# SCH_New_Project4_2022-07-20.net
KiCad netlist of a schematic drawn in EasyEDA
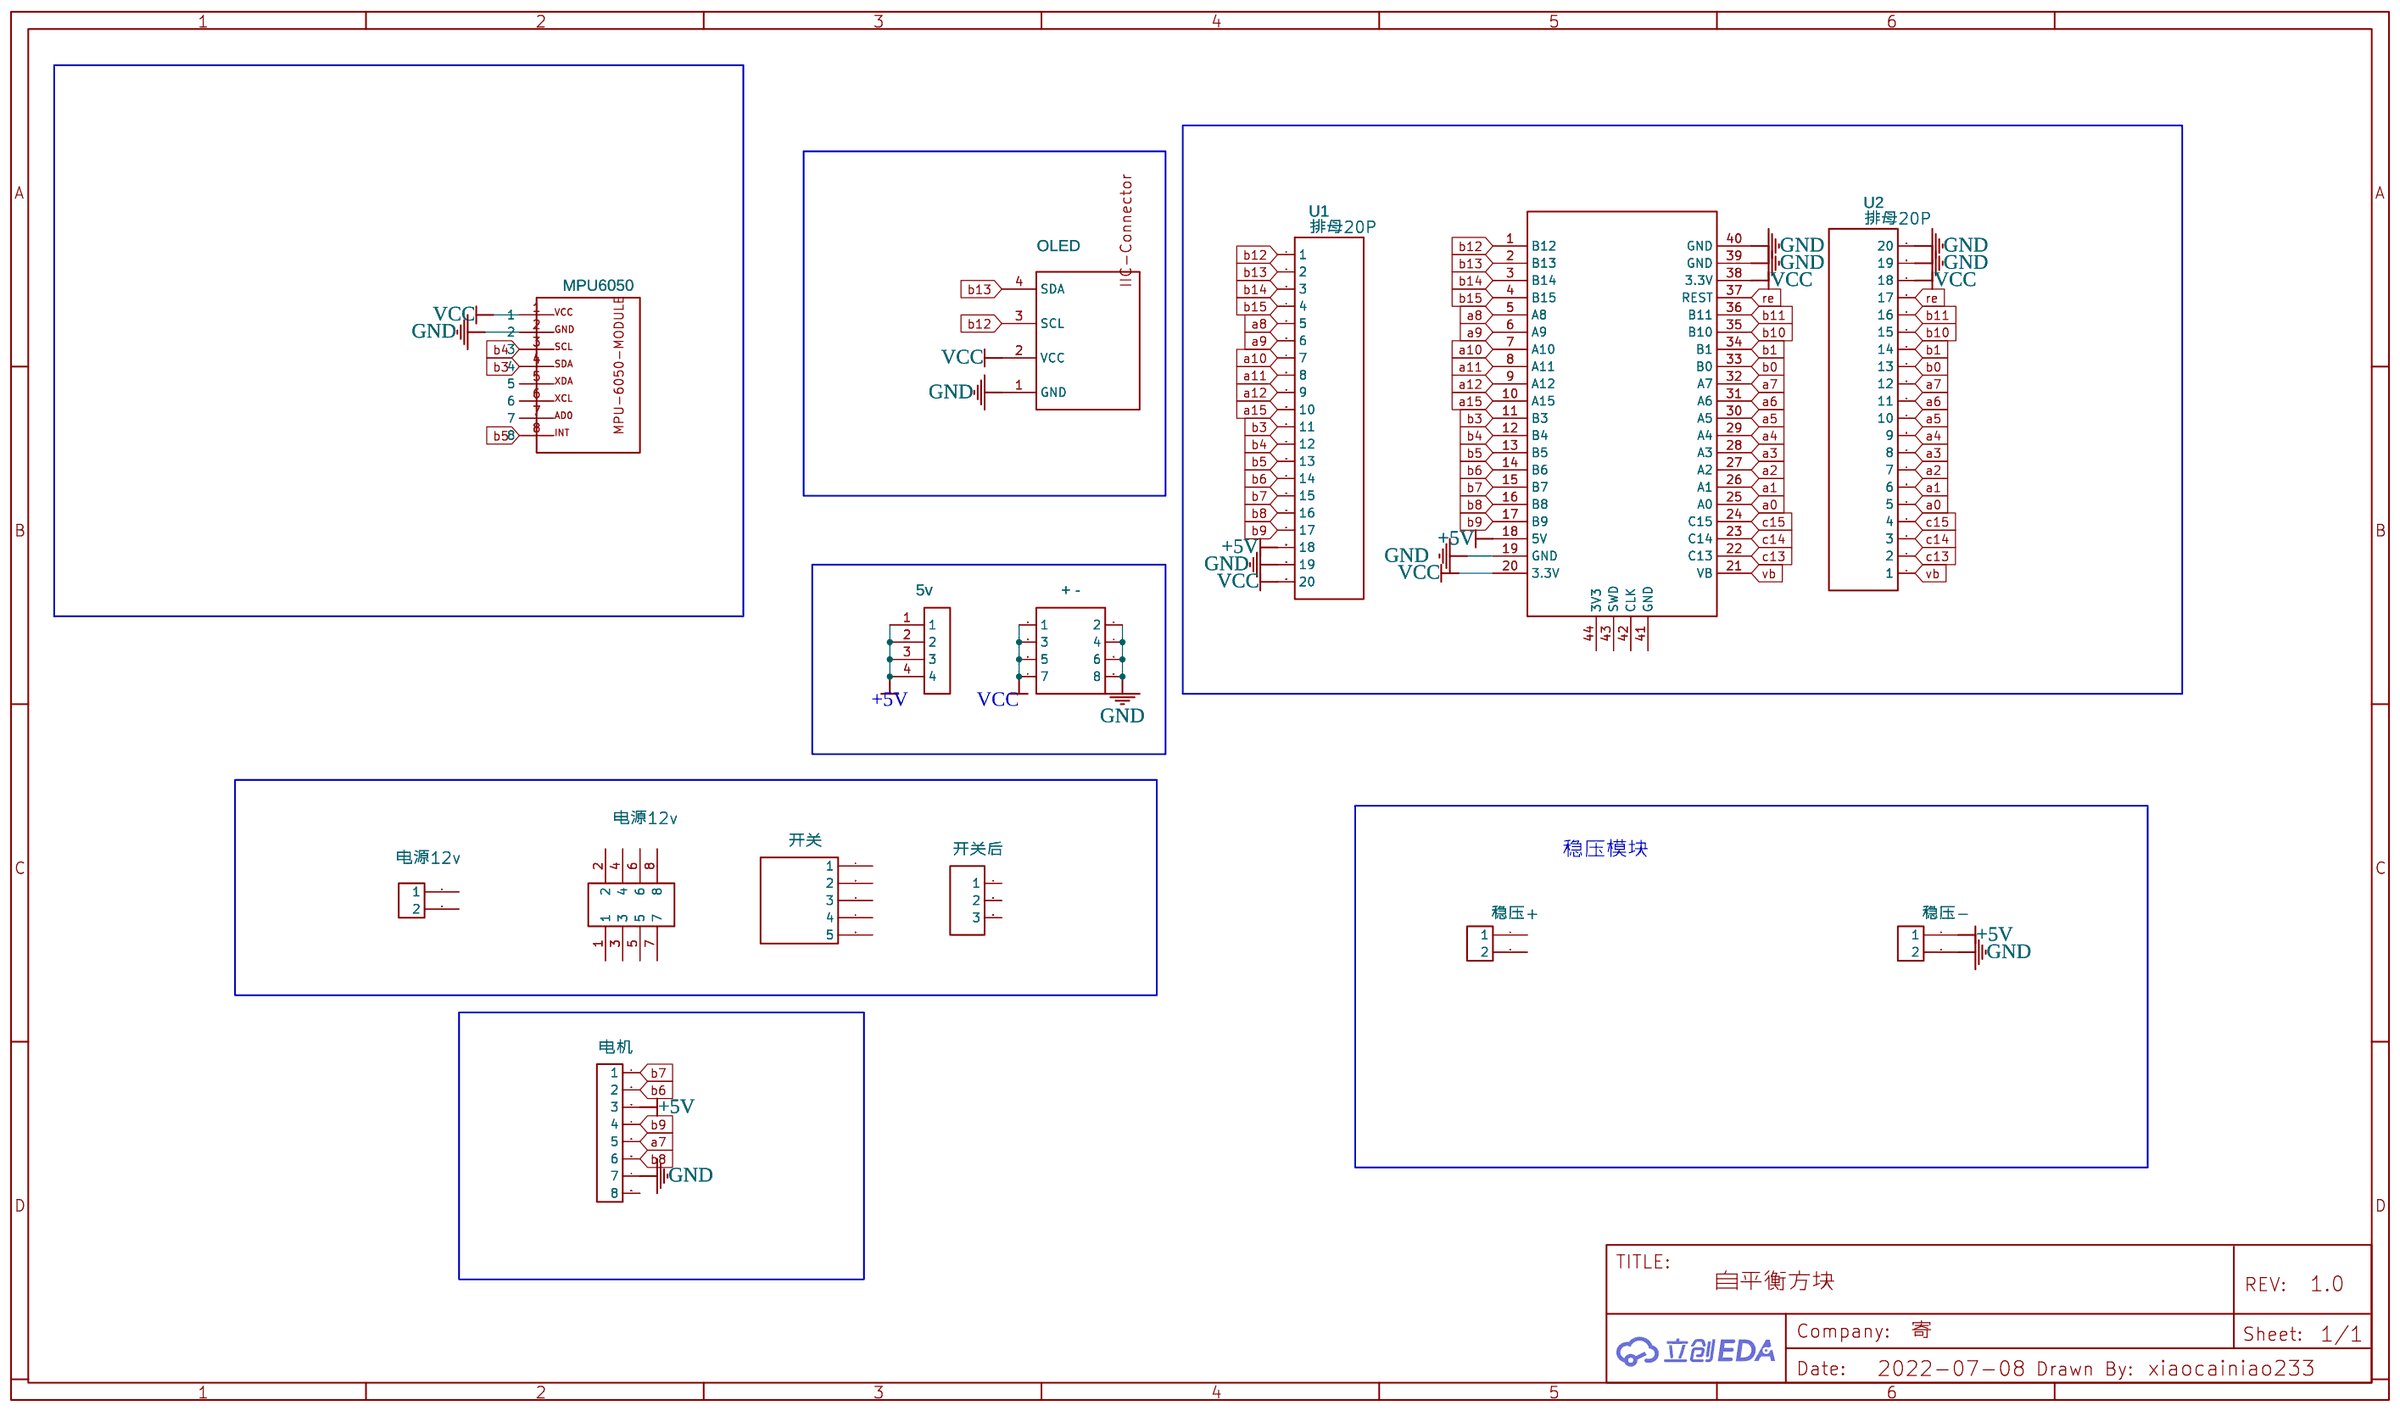
[diagram p0: schematic sheet]

(export (version "E")
  (design (tool "Eeschema 10.0.6"))
  (components
    (comp (ref "AAAAU1") (value "MPU6050") (libsource (lib "") (part "MPU6050")))
    (comp (ref "ASDFGUUU1") (value "STM32F103C8T6最小系统板") (libsource (lib "") (part "Unknown_930_-560")))
    (comp (ref "H1")
      (value "+ -")
      (fields
        (field (name "BOM_Manufacturer Part") "220S-2*4P H=8.5MM Ytype Gold-plated")
        (field (name "BOM_Supplier Part") "C124422")
      )
      (libsource (lib "") (part "2.54排母_2X4"))
    )
    (comp (ref "H2")
      (value "5v")
      (fields (field (name "BOM_Supplier Part") "C169817"))
      (libsource (lib "") (part "排针排母4P"))
    )
    (comp (ref "H3")
      (value "电源12v")
      (fields (field (name "BOM_Supplier Part") "C169817"))
      (libsource (lib "") (part "排针排母2*4P"))
    )
    (comp (ref "J1")
      (value "电源12v")
      (fields (field (name "BOM_Supplier Part") "C115245"))
      (libsource (lib "") (part "排针排母1*2P"))
    )
    (comp (ref "J2")
      (value "开关")
      (fields (field (name "BOM_Supplier Part") "C115245"))
      (libsource (lib "") (part "排针排母1*5P"))
    )
    (comp (ref "J3")
      (value "电机")
      (fields (field (name "BOM_Supplier Part") "C115245"))
      (libsource (lib "") (part "排针排母1*8P"))
    )
    (comp (ref "J4")
      (value "稳压+")
      (fields (field (name "BOM_Supplier Part") "C115245"))
      (libsource (lib "") (part "排针排母1*2P"))
    )
    (comp (ref "J5")
      (value "稳压-")
      (fields (field (name "BOM_Supplier Part") "C115245"))
      (libsource (lib "") (part "排针排母1*2P"))
    )
    (comp (ref "J6")
      (value "开关后")
      (fields (field (name "BOM_Manufacturer Part") "Headers") (field (name "BOM_Supplier Part") "C57369"))
      (libsource (lib "") (part "排针排母1*3P"))
    )
    (comp (ref "OLED")
      (value "0.96OLED")
      (fields
        (field (name "BOM_Manufacturer Part") "0.96OLED_4P_MODULE_JX")
        (field (name "BOM_Supplier Part") "C9900004566")
      )
      (libsource (lib "") (part "0.96OLED_4P_MODULE_JX"))
    )
    (comp (ref "U1") (value "排母20P") (libsource (lib "") (part "排母20P")))
    (comp (ref "U2") (value "排母20P") (libsource (lib "") (part "排母20P_1")))
  )
  (nets
    (net (code "1") (name "+5V") (class "Default")
      (node (ref "ASDFGUUU1") (pin "18") (pinfunction "5V_18") (pintype "unspecified"))
      (node (ref "H2") (pin "1") (pinfunction "1_1") (pintype "unspecified"))
      (node (ref "H2") (pin "2") (pinfunction "2_2") (pintype "unspecified"))
      (node (ref "H2") (pin "3") (pinfunction "3_3") (pintype "unspecified"))
      (node (ref "H2") (pin "4") (pinfunction "4_4") (pintype "unspecified"))
      (node (ref "J3") (pin "3") (pinfunction "3_3") (pintype "unspecified"))
      (node (ref "J5") (pin "1") (pinfunction "1_1") (pintype "unspecified"))
      (node (ref "U1") (pin "18") (pinfunction "18_18") (pintype "input"))
    )
    (net (code "2") (name "GND") (class "Default")
      (node (ref "AAAAU1") (pin "2") (pinfunction "2_2") (pintype "unspecified"))
      (node (ref "ASDFGUUU1") (pin "19") (pinfunction "GND_19") (pintype "unspecified"))
      (node (ref "ASDFGUUU1") (pin "39") (pinfunction "GND_39") (pintype "unspecified"))
      (node (ref "ASDFGUUU1") (pin "40") (pinfunction "GND_40") (pintype "unspecified"))
      (node (ref "H1") (pin "2") (pinfunction "2_2") (pintype "unspecified"))
      (node (ref "H1") (pin "4") (pinfunction "4_4") (pintype "unspecified"))
      (node (ref "H1") (pin "6") (pinfunction "6_6") (pintype "unspecified"))
      (node (ref "H1") (pin "8") (pinfunction "8_8") (pintype "unspecified"))
      (node (ref "J3") (pin "7") (pinfunction "7_7") (pintype "unspecified"))
      (node (ref "J5") (pin "2") (pinfunction "2_2") (pintype "unspecified"))
      (node (ref "OLED") (pin "1") (pinfunction "GND_1") (pintype "unspecified"))
      (node (ref "U1") (pin "19") (pinfunction "19_19") (pintype "input"))
      (node (ref "U2") (pin "19") (pinfunction "19_19") (pintype "input"))
      (node (ref "U2") (pin "20") (pinfunction "20_20") (pintype "input"))
    )
    (net (code "3") (name "VCC") (class "Default")
      (node (ref "AAAAU1") (pin "1") (pinfunction "1_1") (pintype "unspecified"))
      (node (ref "ASDFGUUU1") (pin "20") (pinfunction "3.3V_20") (pintype "unspecified"))
      (node (ref "ASDFGUUU1") (pin "38") (pinfunction "3.3V_38") (pintype "unspecified"))
      (node (ref "H1") (pin "1") (pinfunction "1_1") (pintype "unspecified"))
      (node (ref "H1") (pin "3") (pinfunction "3_3") (pintype "unspecified"))
      (node (ref "H1") (pin "5") (pinfunction "5_5") (pintype "unspecified"))
      (node (ref "H1") (pin "7") (pinfunction "7_7") (pintype "unspecified"))
      (node (ref "OLED") (pin "2") (pinfunction "VCC_2") (pintype "unspecified"))
      (node (ref "U1") (pin "20") (pinfunction "20_20") (pintype "input"))
      (node (ref "U2") (pin "18") (pinfunction "18_18") (pintype "input"))
    )
    (net (code "4") (name "a0") (class "Default")
      (node (ref "ASDFGUUU1") (pin "25") (pinfunction "A0_25") (pintype "unspecified"))
      (node (ref "U2") (pin "5") (pinfunction "5_5") (pintype "input"))
    )
    (net (code "5") (name "a1") (class "Default")
      (node (ref "ASDFGUUU1") (pin "26") (pinfunction "A1_26") (pintype "unspecified"))
      (node (ref "U2") (pin "6") (pinfunction "6_6") (pintype "input"))
    )
    (net (code "6") (name "a2") (class "Default")
      (node (ref "ASDFGUUU1") (pin "27") (pinfunction "A2_27") (pintype "unspecified"))
      (node (ref "U2") (pin "7") (pinfunction "7_7") (pintype "input"))
    )
    (net (code "7") (name "a3") (class "Default")
      (node (ref "ASDFGUUU1") (pin "28") (pinfunction "A3_28") (pintype "unspecified"))
      (node (ref "U2") (pin "8") (pinfunction "8_8") (pintype "input"))
    )
    (net (code "8") (name "a4") (class "Default")
      (node (ref "ASDFGUUU1") (pin "29") (pinfunction "A4_29") (pintype "unspecified"))
      (node (ref "U2") (pin "9") (pinfunction "9_9") (pintype "input"))
    )
    (net (code "9") (name "a5") (class "Default")
      (node (ref "ASDFGUUU1") (pin "30") (pinfunction "A5_30") (pintype "unspecified"))
      (node (ref "U2") (pin "10") (pinfunction "10_10") (pintype "input"))
    )
    (net (code "10") (name "a6") (class "Default")
      (node (ref "ASDFGUUU1") (pin "31") (pinfunction "A6_31") (pintype "unspecified"))
      (node (ref "U2") (pin "11") (pinfunction "11_11") (pintype "input"))
    )
    (net (code "11") (name "a7") (class "Default")
      (node (ref "ASDFGUUU1") (pin "32") (pinfunction "A7_32") (pintype "unspecified"))
      (node (ref "J3") (pin "5") (pinfunction "5_5") (pintype "unspecified"))
      (node (ref "U2") (pin "12") (pinfunction "12_12") (pintype "input"))
    )
    (net (code "12") (name "a8") (class "Default")
      (node (ref "ASDFGUUU1") (pin "5") (pinfunction "A8_5") (pintype "unspecified"))
      (node (ref "U1") (pin "5") (pinfunction "5_5") (pintype "input"))
    )
    (net (code "13") (name "a9") (class "Default")
      (node (ref "ASDFGUUU1") (pin "6") (pinfunction "A9_6") (pintype "unspecified"))
      (node (ref "U1") (pin "6") (pinfunction "6_6") (pintype "input"))
    )
    (net (code "14") (name "a10") (class "Default")
      (node (ref "ASDFGUUU1") (pin "7") (pinfunction "A10_7") (pintype "unspecified"))
      (node (ref "U1") (pin "7") (pinfunction "7_7") (pintype "input"))
    )
    (net (code "15") (name "a11") (class "Default")
      (node (ref "ASDFGUUU1") (pin "8") (pinfunction "A11_8") (pintype "unspecified"))
      (node (ref "U1") (pin "8") (pinfunction "8_8") (pintype "input"))
    )
    (net (code "16") (name "a12") (class "Default")
      (node (ref "ASDFGUUU1") (pin "9") (pinfunction "A12_9") (pintype "unspecified"))
      (node (ref "U1") (pin "9") (pinfunction "9_9") (pintype "input"))
    )
    (net (code "17") (name "a15") (class "Default")
      (node (ref "ASDFGUUU1") (pin "10") (pinfunction "A15_10") (pintype "unspecified"))
      (node (ref "U1") (pin "10") (pinfunction "10_10") (pintype "input"))
    )
    (net (code "18") (name "b0") (class "Default")
      (node (ref "ASDFGUUU1") (pin "33") (pinfunction "B0_33") (pintype "unspecified"))
      (node (ref "U2") (pin "13") (pinfunction "13_13") (pintype "input"))
    )
    (net (code "19") (name "b1") (class "Default")
      (node (ref "ASDFGUUU1") (pin "34") (pinfunction "B1_34") (pintype "unspecified"))
      (node (ref "U2") (pin "14") (pinfunction "14_14") (pintype "input"))
    )
    (net (code "20") (name "b3") (class "Default")
      (node (ref "AAAAU1") (pin "4") (pinfunction "4_4") (pintype "unspecified"))
      (node (ref "ASDFGUUU1") (pin "11") (pinfunction "B3_11") (pintype "unspecified"))
      (node (ref "U1") (pin "11") (pinfunction "11_11") (pintype "input"))
    )
    (net (code "21") (name "b4") (class "Default")
      (node (ref "AAAAU1") (pin "3") (pinfunction "3_3") (pintype "unspecified"))
      (node (ref "ASDFGUUU1") (pin "12") (pinfunction "B4_12") (pintype "unspecified"))
      (node (ref "U1") (pin "12") (pinfunction "12_12") (pintype "input"))
    )
    (net (code "22") (name "b5") (class "Default")
      (node (ref "AAAAU1") (pin "8") (pinfunction "8_8") (pintype "unspecified"))
      (node (ref "ASDFGUUU1") (pin "13") (pinfunction "B5_13") (pintype "unspecified"))
      (node (ref "U1") (pin "13") (pinfunction "13_13") (pintype "input"))
    )
    (net (code "23") (name "b6") (class "Default")
      (node (ref "ASDFGUUU1") (pin "14") (pinfunction "B6_14") (pintype "unspecified"))
      (node (ref "J3") (pin "2") (pinfunction "2_2") (pintype "unspecified"))
      (node (ref "U1") (pin "14") (pinfunction "14_14") (pintype "input"))
    )
    (net (code "24") (name "b7") (class "Default")
      (node (ref "ASDFGUUU1") (pin "15") (pinfunction "B7_15") (pintype "unspecified"))
      (node (ref "J3") (pin "1") (pinfunction "1_1") (pintype "unspecified"))
      (node (ref "U1") (pin "15") (pinfunction "15_15") (pintype "input"))
    )
    (net (code "25") (name "b8") (class "Default")
      (node (ref "ASDFGUUU1") (pin "16") (pinfunction "B8_16") (pintype "unspecified"))
      (node (ref "J3") (pin "6") (pinfunction "6_6") (pintype "unspecified"))
      (node (ref "U1") (pin "16") (pinfunction "16_16") (pintype "input"))
    )
    (net (code "26") (name "b9") (class "Default")
      (node (ref "ASDFGUUU1") (pin "17") (pinfunction "B9_17") (pintype "unspecified"))
      (node (ref "J3") (pin "4") (pinfunction "4_4") (pintype "unspecified"))
      (node (ref "U1") (pin "17") (pinfunction "17_17") (pintype "input"))
    )
    (net (code "27") (name "b10") (class "Default")
      (node (ref "ASDFGUUU1") (pin "35") (pinfunction "B10_35") (pintype "unspecified"))
      (node (ref "U2") (pin "15") (pinfunction "15_15") (pintype "input"))
    )
    (net (code "28") (name "b11") (class "Default")
      (node (ref "ASDFGUUU1") (pin "36") (pinfunction "B11_36") (pintype "unspecified"))
      (node (ref "U2") (pin "16") (pinfunction "16_16") (pintype "input"))
    )
    (net (code "29") (name "b12") (class "Default")
      (node (ref "ASDFGUUU1") (pin "1") (pinfunction "B12_1") (pintype "unspecified"))
      (node (ref "OLED") (pin "3") (pinfunction "SCL_3") (pintype "unspecified"))
      (node (ref "U1") (pin "1") (pinfunction "1_1") (pintype "input"))
    )
    (net (code "30") (name "b13") (class "Default")
      (node (ref "ASDFGUUU1") (pin "2") (pinfunction "B13_2") (pintype "unspecified"))
      (node (ref "OLED") (pin "4") (pinfunction "SDA_4") (pintype "unspecified"))
      (node (ref "U1") (pin "2") (pinfunction "2_2") (pintype "input"))
    )
    (net (code "31") (name "b14") (class "Default")
      (node (ref "ASDFGUUU1") (pin "3") (pinfunction "B14_3") (pintype "unspecified"))
      (node (ref "U1") (pin "3") (pinfunction "3_3") (pintype "input"))
    )
    (net (code "32") (name "b15") (class "Default")
      (node (ref "ASDFGUUU1") (pin "4") (pinfunction "B15_4") (pintype "unspecified"))
      (node (ref "U1") (pin "4") (pinfunction "4_4") (pintype "input"))
    )
    (net (code "33") (name "c13") (class "Default")
      (node (ref "ASDFGUUU1") (pin "22") (pinfunction "C13_22") (pintype "unspecified"))
      (node (ref "U2") (pin "2") (pinfunction "2_2") (pintype "input"))
    )
    (net (code "34") (name "c14") (class "Default")
      (node (ref "ASDFGUUU1") (pin "23") (pinfunction "C14_23") (pintype "unspecified"))
      (node (ref "U2") (pin "3") (pinfunction "3_3") (pintype "input"))
    )
    (net (code "35") (name "c15") (class "Default")
      (node (ref "ASDFGUUU1") (pin "24") (pinfunction "C15_24") (pintype "unspecified"))
      (node (ref "U2") (pin "4") (pinfunction "4_4") (pintype "input"))
    )
    (net (code "36") (name "re") (class "Default")
      (node (ref "ASDFGUUU1") (pin "37") (pinfunction "REST_37") (pintype "unspecified"))
      (node (ref "U2") (pin "17") (pinfunction "17_17") (pintype "input"))
    )
    (net (code "37") (name "unconnected-(AAAAU1-Pad5)") (class "Default")
      (node (ref "AAAAU1") (pin "5") (pinfunction "5_5") (pintype "unspecified"))
    )
    (net (code "38") (name "unconnected-(AAAAU1-Pad6)") (class "Default")
      (node (ref "AAAAU1") (pin "6") (pinfunction "6_6") (pintype "unspecified"))
    )
    (net (code "39") (name "unconnected-(AAAAU1-Pad7)") (class "Default")
      (node (ref "AAAAU1") (pin "7") (pinfunction "7_7") (pintype "unspecified"))
    )
    (net (code "40") (name "unconnected-(ASDFGUUU1-3V3-Pad44)") (class "Default")
      (node (ref "ASDFGUUU1") (pin "44") (pinfunction "3V3_44") (pintype "unspecified"))
    )
    (net (code "41") (name "unconnected-(ASDFGUUU1-CLK-Pad42)") (class "Default")
      (node (ref "ASDFGUUU1") (pin "42") (pinfunction "CLK_42") (pintype "unspecified"))
    )
    (net (code "42") (name "unconnected-(ASDFGUUU1-GND-Pad41)") (class "Default")
      (node (ref "ASDFGUUU1") (pin "41") (pinfunction "GND_41") (pintype "unspecified"))
    )
    (net (code "43") (name "unconnected-(ASDFGUUU1-SWD-Pad43)") (class "Default")
      (node (ref "ASDFGUUU1") (pin "43") (pinfunction "SWD_43") (pintype "unspecified"))
    )
    (net (code "44") (name "unconnected-(H3-Pad1)") (class "Default")
      (node (ref "H3") (pin "1") (pinfunction "1_1") (pintype "unspecified"))
    )
    (net (code "45") (name "unconnected-(H3-Pad2)") (class "Default")
      (node (ref "H3") (pin "2") (pinfunction "2_2") (pintype "unspecified"))
    )
    (net (code "46") (name "unconnected-(H3-Pad3)") (class "Default")
      (node (ref "H3") (pin "3") (pinfunction "3_3") (pintype "unspecified"))
    )
    (net (code "47") (name "unconnected-(H3-Pad4)") (class "Default")
      (node (ref "H3") (pin "4") (pinfunction "4_4") (pintype "unspecified"))
    )
    (net (code "48") (name "unconnected-(H3-Pad5)") (class "Default")
      (node (ref "H3") (pin "5") (pinfunction "5_5") (pintype "unspecified"))
    )
    (net (code "49") (name "unconnected-(H3-Pad6)") (class "Default")
      (node (ref "H3") (pin "6") (pinfunction "6_6") (pintype "unspecified"))
    )
    (net (code "50") (name "unconnected-(H3-Pad7)") (class "Default")
      (node (ref "H3") (pin "7") (pinfunction "7_7") (pintype "unspecified"))
    )
    (net (code "51") (name "unconnected-(H3-Pad8)") (class "Default")
      (node (ref "H3") (pin "8") (pinfunction "8_8") (pintype "unspecified"))
    )
    (net (code "52") (name "unconnected-(J1-Pad1)") (class "Default")
      (node (ref "J1") (pin "1") (pinfunction "1_1") (pintype "unspecified"))
    )
    (net (code "53") (name "unconnected-(J1-Pad2)") (class "Default")
      (node (ref "J1") (pin "2") (pinfunction "2_2") (pintype "unspecified"))
    )
    (net (code "54") (name "unconnected-(J2-Pad1)") (class "Default")
      (node (ref "J2") (pin "1") (pinfunction "1_1") (pintype "unspecified"))
    )
    (net (code "55") (name "unconnected-(J2-Pad2)") (class "Default")
      (node (ref "J2") (pin "2") (pinfunction "2_2") (pintype "unspecified"))
    )
    (net (code "56") (name "unconnected-(J2-Pad3)") (class "Default")
      (node (ref "J2") (pin "3") (pinfunction "3_3") (pintype "unspecified"))
    )
    (net (code "57") (name "unconnected-(J2-Pad4)") (class "Default")
      (node (ref "J2") (pin "4") (pinfunction "4_4") (pintype "unspecified"))
    )
    (net (code "58") (name "unconnected-(J2-Pad5)") (class "Default")
      (node (ref "J2") (pin "5") (pinfunction "5_5") (pintype "unspecified"))
    )
    (net (code "59") (name "unconnected-(J3-Pad8)") (class "Default")
      (node (ref "J3") (pin "8") (pinfunction "8_8") (pintype "unspecified"))
    )
    (net (code "60") (name "unconnected-(J4-Pad1)") (class "Default")
      (node (ref "J4") (pin "1") (pinfunction "1_1") (pintype "unspecified"))
    )
    (net (code "61") (name "unconnected-(J4-Pad2)") (class "Default")
      (node (ref "J4") (pin "2") (pinfunction "2_2") (pintype "unspecified"))
    )
    (net (code "62") (name "unconnected-(J6-Pad1)") (class "Default")
      (node (ref "J6") (pin "1") (pinfunction "1_1") (pintype "input"))
    )
    (net (code "63") (name "unconnected-(J6-Pad2)") (class "Default")
      (node (ref "J6") (pin "2") (pinfunction "2_2") (pintype "input"))
    )
    (net (code "64") (name "unconnected-(J6-Pad3)") (class "Default")
      (node (ref "J6") (pin "3") (pinfunction "3_3") (pintype "input"))
    )
    (net (code "65") (name "vb") (class "Default")
      (node (ref "ASDFGUUU1") (pin "21") (pinfunction "VB_21") (pintype "unspecified"))
      (node (ref "U2") (pin "1") (pinfunction "1_1") (pintype "input"))
    )
  )
)
